# SparrowAprs.net
KiCad netlist of a schematic drawn in EAGLE
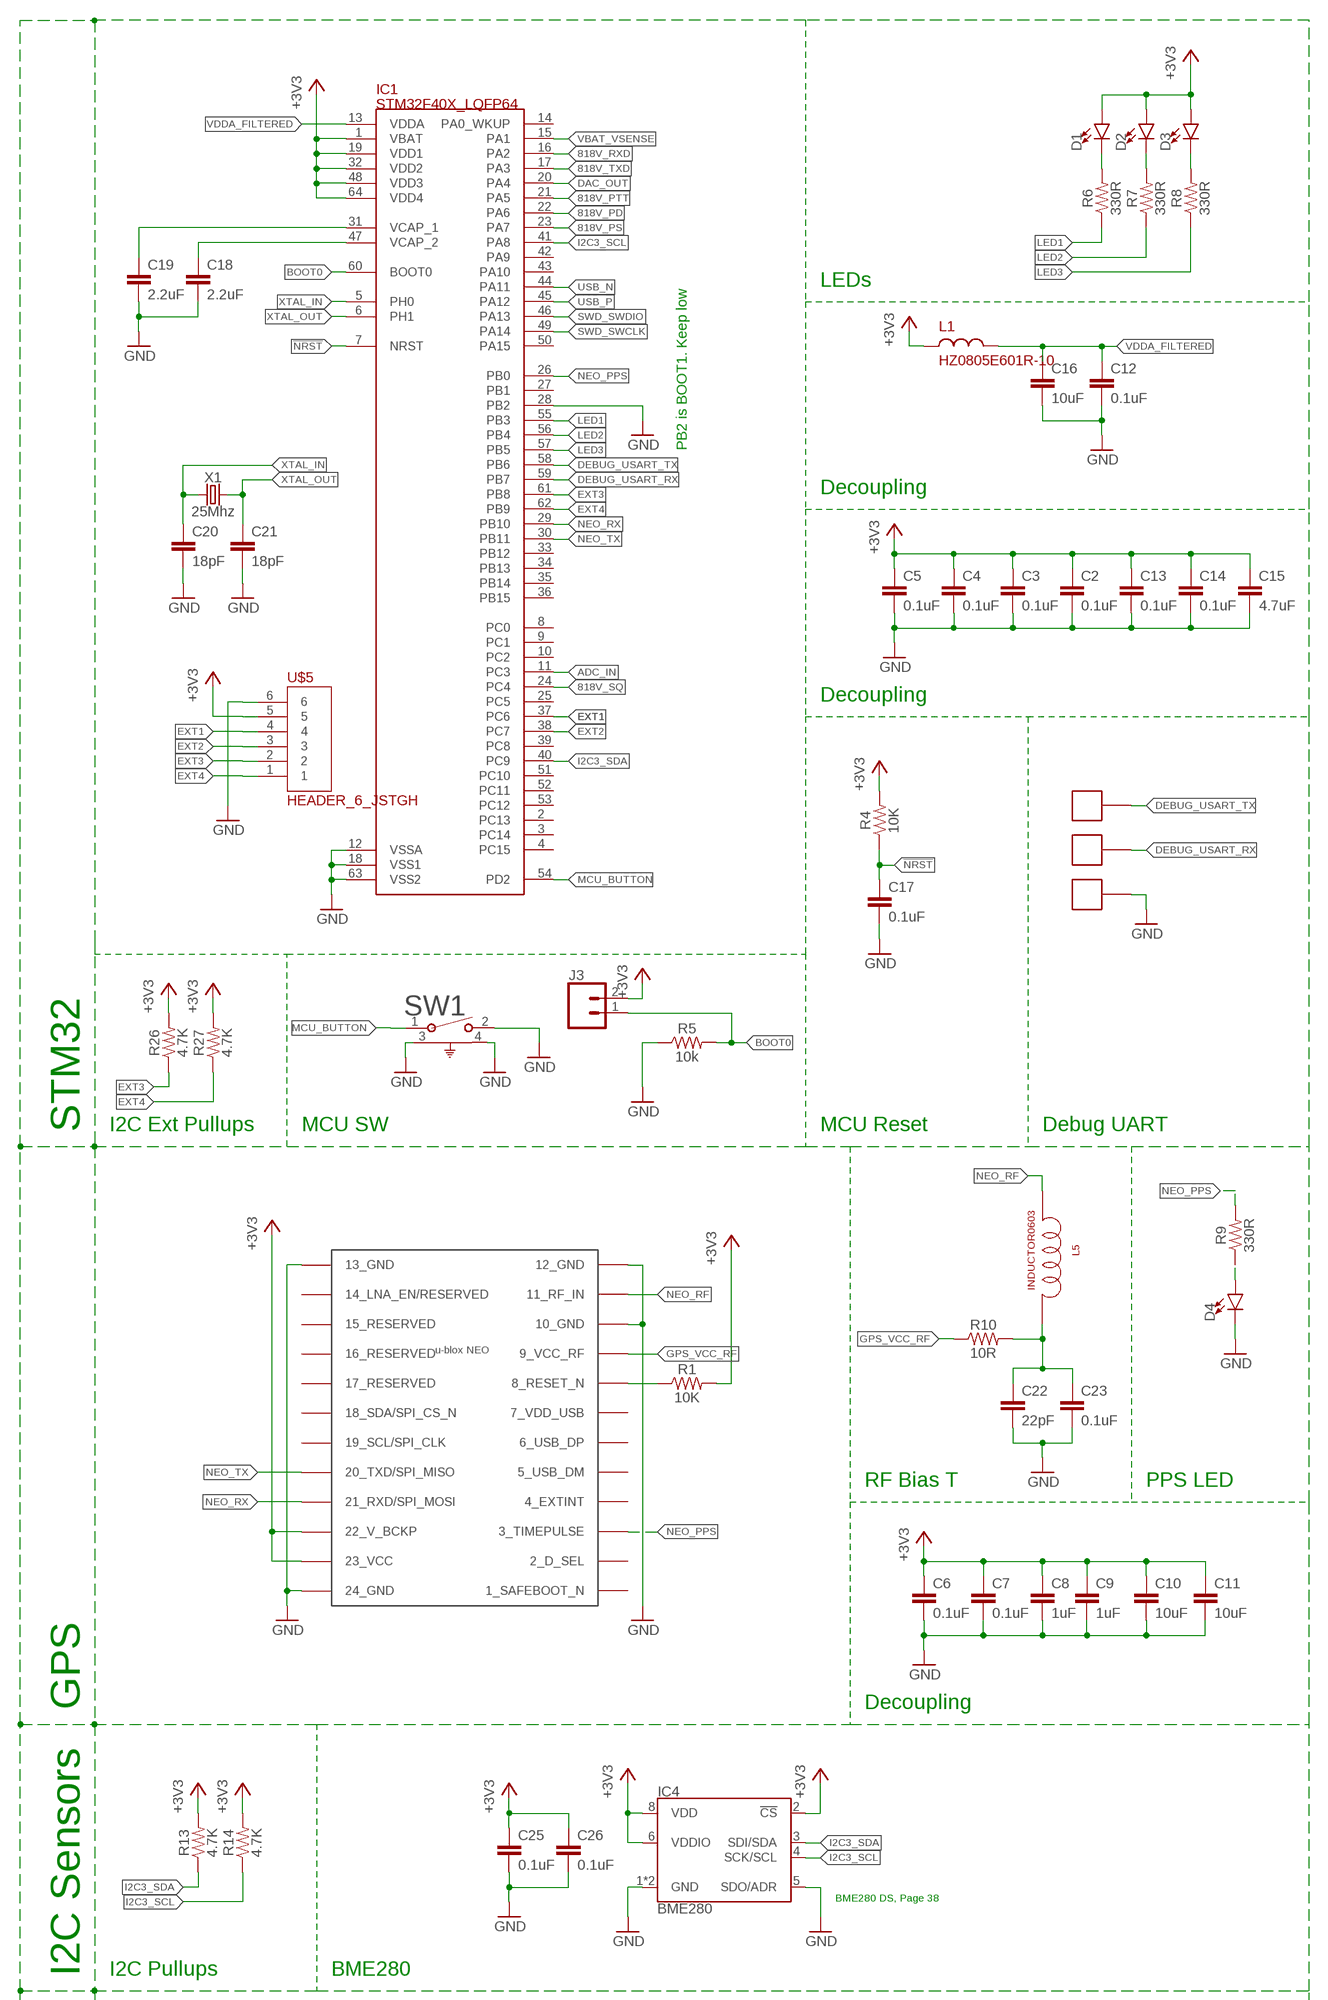
[diagram p0: schematic, sheet 1, part 1 of 2]
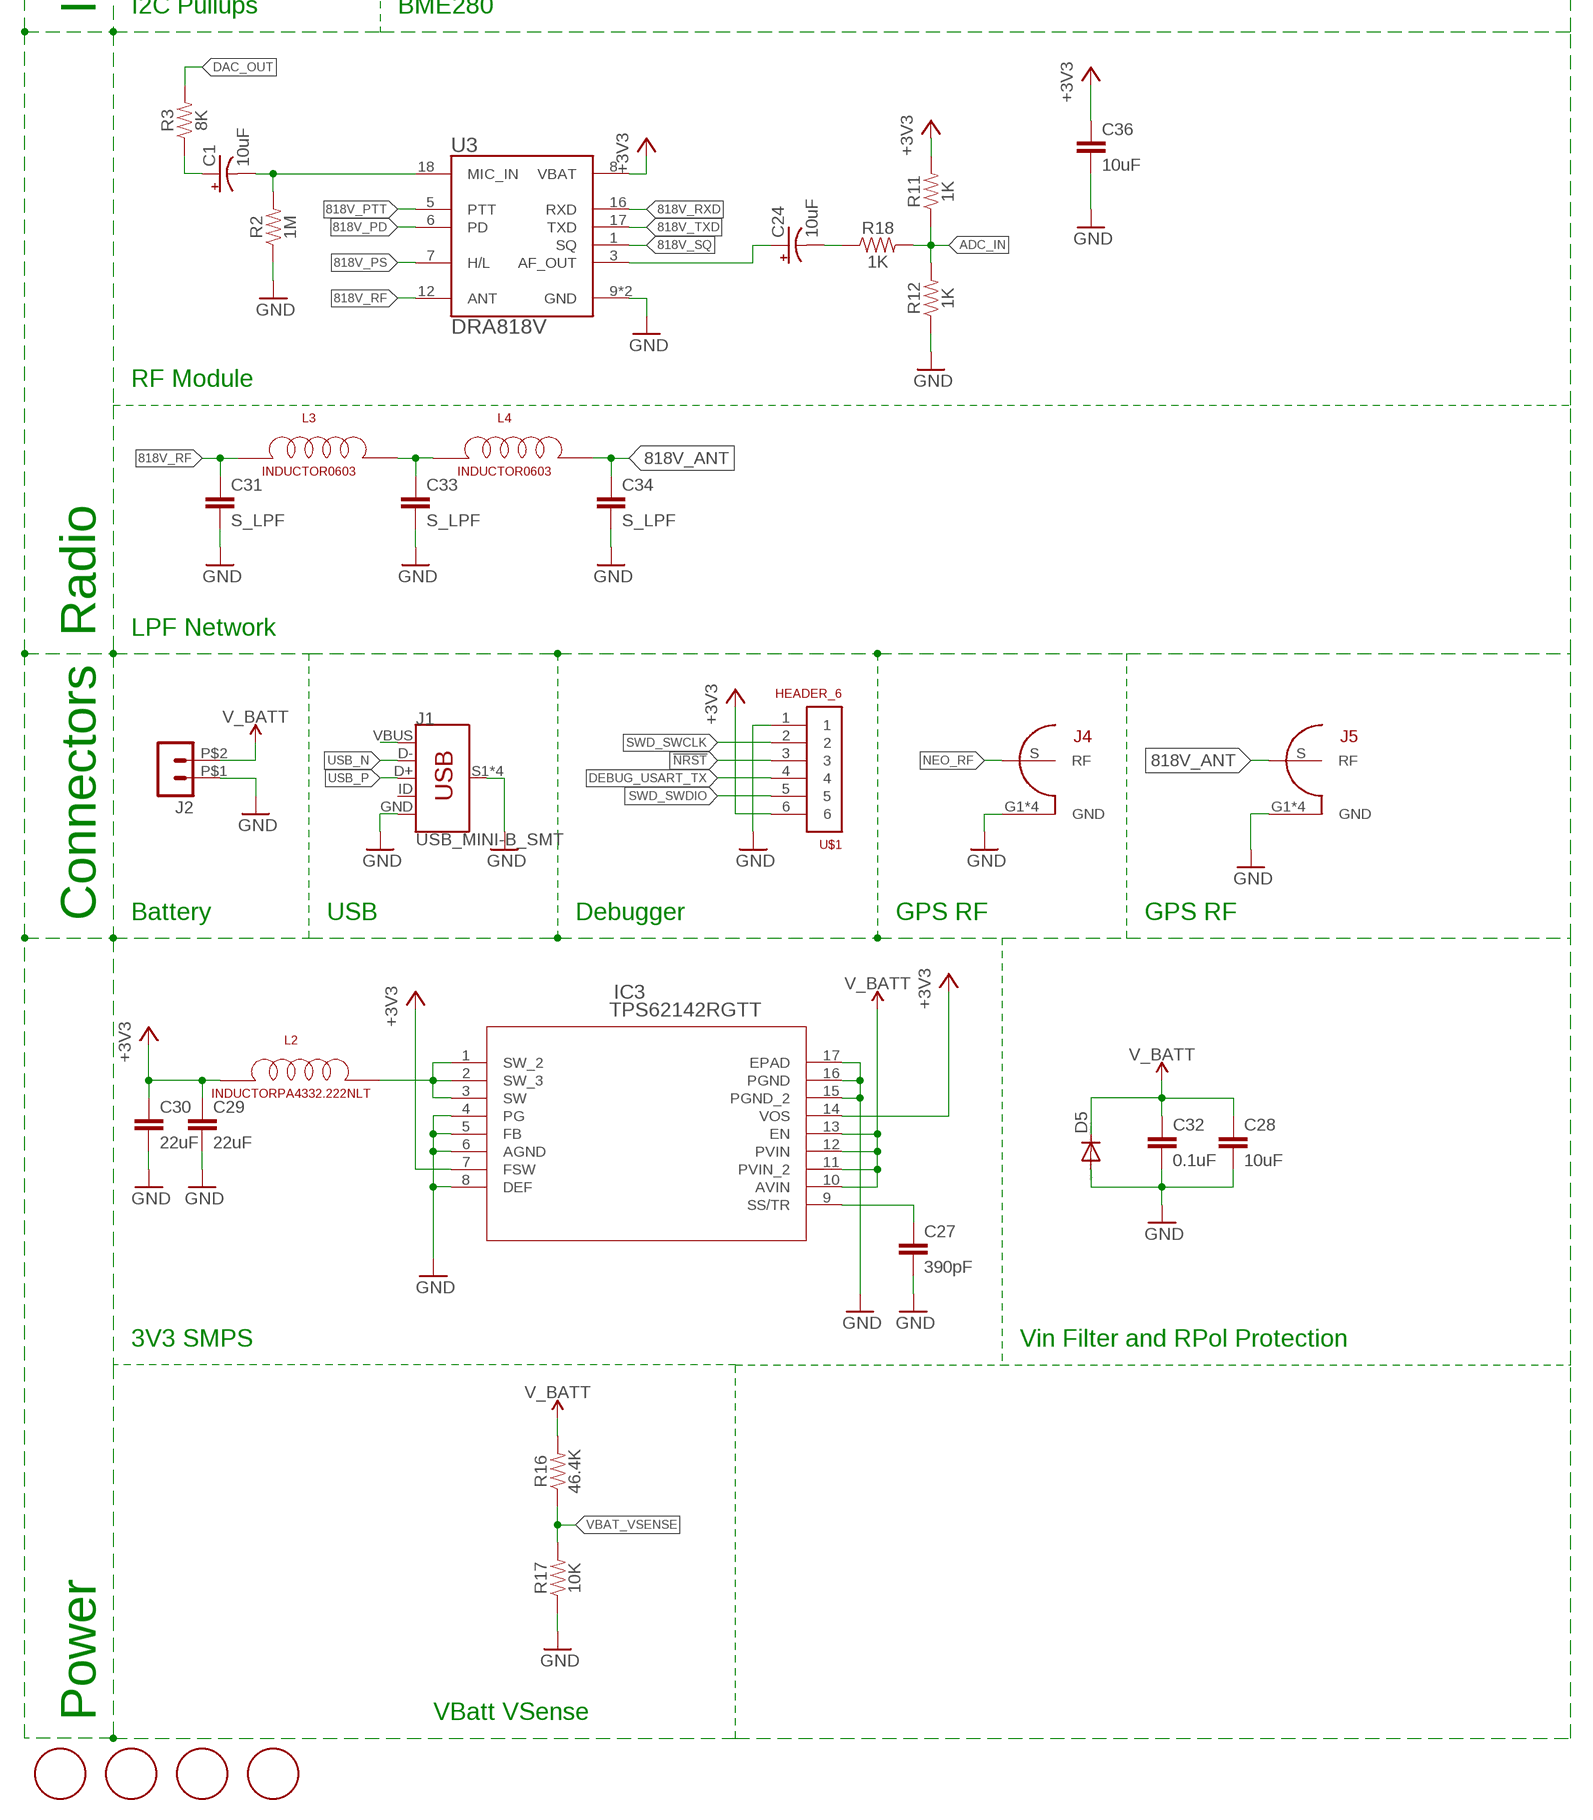
[diagram p1: schematic, sheet 1, part 2 of 2]

(export (version "E")
  (design (tool "Eeschema 10.0.6"))
  (components
    (comp (ref "C1")
      (value "10uF")
      (footprint "eagle-import:1206")
      (libsource (lib "eagle-import") (part "CAP_POL1206_POL"))
    )
    (comp (ref "C2")
      (value "0.1uF")
      (footprint "eagle-import:0603")
      (libsource (lib "eagle-import") (part "CAP0603"))
    )
    (comp (ref "C3")
      (value "0.1uF")
      (footprint "eagle-import:0603")
      (libsource (lib "eagle-import") (part "CAP0603"))
    )
    (comp (ref "C4")
      (value "0.1uF")
      (footprint "eagle-import:0603")
      (libsource (lib "eagle-import") (part "CAP0603"))
    )
    (comp (ref "C5")
      (value "0.1uF")
      (footprint "eagle-import:0603")
      (libsource (lib "eagle-import") (part "CAP0603"))
    )
    (comp (ref "C6")
      (value "0.1uF")
      (footprint "eagle-import:0603")
      (libsource (lib "eagle-import") (part "CAP0603"))
    )
    (comp (ref "C7")
      (value "0.1uF")
      (footprint "eagle-import:0603")
      (libsource (lib "eagle-import") (part "CAP0603"))
    )
    (comp (ref "C8")
      (value "1uF")
      (footprint "eagle-import:C0805")
      (libsource (lib "eagle-import") (part "C-EUC0805"))
    )
    (comp (ref "C9")
      (value "1uF")
      (footprint "eagle-import:C0805")
      (libsource (lib "eagle-import") (part "C-EUC0805"))
    )
    (comp (ref "C10")
      (value "10uF")
      (footprint "eagle-import:C0805")
      (libsource (lib "eagle-import") (part "C-EUC0805"))
    )
    (comp (ref "C11")
      (value "10uF")
      (footprint "eagle-import:C0805")
      (libsource (lib "eagle-import") (part "C-EUC0805"))
    )
    (comp (ref "C12")
      (value "0.1uF")
      (footprint "eagle-import:0603")
      (libsource (lib "eagle-import") (part "CAP0603"))
    )
    (comp (ref "C13")
      (value "0.1uF")
      (footprint "eagle-import:0603")
      (libsource (lib "eagle-import") (part "CAP0603"))
    )
    (comp (ref "C14")
      (value "0.1uF")
      (footprint "eagle-import:0603")
      (libsource (lib "eagle-import") (part "CAP0603"))
    )
    (comp (ref "C15")
      (value "4.7uF")
      (footprint "eagle-import:C0805")
      (libsource (lib "eagle-import") (part "C-EUC0805"))
    )
    (comp (ref "C16")
      (value "10uF")
      (footprint "eagle-import:C0805")
      (libsource (lib "eagle-import") (part "C-EUC0805"))
    )
    (comp (ref "C17")
      (value "0.1uF")
      (footprint "eagle-import:0603")
      (libsource (lib "eagle-import") (part "CAP0603"))
    )
    (comp (ref "C18")
      (value "2.2uF")
      (footprint "eagle-import:C0805")
      (libsource (lib "eagle-import") (part "C-EUC0805"))
    )
    (comp (ref "C19")
      (value "2.2uF")
      (footprint "eagle-import:C0805")
      (libsource (lib "eagle-import") (part "C-EUC0805"))
    )
    (comp (ref "C20")
      (value "18pF")
      (footprint "eagle-import:0603")
      (libsource (lib "eagle-import") (part "CAP0603"))
    )
    (comp (ref "C21")
      (value "18pF")
      (footprint "eagle-import:0603")
      (libsource (lib "eagle-import") (part "CAP0603"))
    )
    (comp (ref "C22")
      (value "22pF")
      (footprint "eagle-import:0603")
      (libsource (lib "eagle-import") (part "CAP0603"))
    )
    (comp (ref "C23")
      (value "0.1uF")
      (footprint "eagle-import:0603")
      (libsource (lib "eagle-import") (part "CAP0603"))
    )
    (comp (ref "C24")
      (value "10uF")
      (footprint "eagle-import:1206")
      (libsource (lib "eagle-import") (part "CAP_POL1206_POL"))
    )
    (comp (ref "C25")
      (value "0.1uF")
      (footprint "eagle-import:0603")
      (libsource (lib "eagle-import") (part "CAP0603"))
    )
    (comp (ref "C26")
      (value "0.1uF")
      (footprint "eagle-import:0603")
      (libsource (lib "eagle-import") (part "CAP0603"))
    )
    (comp (ref "C27")
      (value "390pF")
      (footprint "eagle-import:0603")
      (libsource (lib "eagle-import") (part "CAP0603"))
    )
    (comp (ref "C28")
      (value "10uF")
      (footprint "eagle-import:C0805")
      (libsource (lib "eagle-import") (part "C-EUC0805"))
    )
    (comp (ref "C29")
      (value "22uF")
      (footprint "eagle-import:1210")
      (libsource (lib "eagle-import") (part "CAP1210"))
    )
    (comp (ref "C30")
      (value "22uF")
      (footprint "eagle-import:1210")
      (libsource (lib "eagle-import") (part "CAP1210"))
    )
    (comp (ref "C31")
      (value "S_LPF")
      (footprint "eagle-import:0603")
      (libsource (lib "eagle-import") (part "CAP0603"))
    )
    (comp (ref "C32")
      (value "0.1uF")
      (footprint "eagle-import:0603")
      (libsource (lib "eagle-import") (part "CAP0603"))
    )
    (comp (ref "C33")
      (value "S_LPF")
      (footprint "eagle-import:0603")
      (libsource (lib "eagle-import") (part "CAP0603"))
    )
    (comp (ref "C34")
      (value "S_LPF")
      (footprint "eagle-import:0603")
      (libsource (lib "eagle-import") (part "CAP0603"))
    )
    (comp (ref "C36")
      (value "10uF")
      (footprint "eagle-import:C0805")
      (libsource (lib "eagle-import") (part "C-EUC0805"))
    )
    (comp (ref "D1")
      (value "LED0603")
      (footprint "eagle-import:LED-0603")
      (libsource (lib "eagle-import") (part "LED0603"))
    )
    (comp (ref "D2")
      (value "LED0603")
      (footprint "eagle-import:LED-0603")
      (libsource (lib "eagle-import") (part "LED0603"))
    )
    (comp (ref "D3")
      (value "LED0603")
      (footprint "eagle-import:LED-0603")
      (libsource (lib "eagle-import") (part "LED0603"))
    )
    (comp (ref "D4")
      (value "LED0603")
      (footprint "eagle-import:LED-0603")
      (libsource (lib "eagle-import") (part "LED0603"))
    )
    (comp (ref "D5")
      (value "DIODE-DO214AC")
      (footprint "eagle-import:DO214AC")
      (libsource (lib "eagle-import") (part "DIODE-DO214AC"))
    )
    (comp (ref "IC1")
      (value "STM32F40X_LQFP64")
      (footprint "eagle-import:STM32_LQFP64")
      (libsource (lib "eagle-import") (part "STM32F40X_LQFP64"))
    )
    (comp (ref "IC2")
      (value "NEO-M8")
      (footprint "eagle-import:NEO-M8")
      (libsource (lib "eagle-import") (part "NEO-M8"))
    )
    (comp (ref "IC3")
      (value "TPS62142RGTT")
      (footprint "eagle-import:RGT16_1P7X1P7")
      (libsource (lib "eagle-import") (part "TPS62142RGTT"))
    )
    (comp (ref "IC4")
      (value "BME280")
      (footprint "eagle-import:LGA-8-2.5X2.5")
      (libsource (lib "eagle-import") (part "BME280"))
    )
    (comp (ref "J1")
      (value "USB_MINI-B_SMT")
      (footprint "eagle-import:USB-MINIB")
      (libsource (lib "eagle-import") (part "USB_MINI-B_SMT"))
    )
    (comp (ref "J2")
      (value "HEADER_POS2_43650-0200")
      (footprint "eagle-import:43650-0200")
      (libsource (lib "eagle-import") (part "HEADER_POS2_?43650-0200"))
    )
    (comp (ref "J3")
      (value "CONN_02")
      (footprint "eagle-import:1X02")
      (libsource (lib "eagle-import") (part "CONN_02"))
    )
    (comp (ref "J4")
      (value "FSK_RUARK2_SMA_0732511150")
      (footprint "eagle-import:FSK_RUARK2_WIDE_SMA")
      (libsource (lib "eagle-import") (part "FSK_RUARK2_SMA_0732511150"))
    )
    (comp (ref "J5")
      (value "FSK_RUARK2_SMA_0732511150")
      (footprint "eagle-import:FSK_RUARK2_WIDE_SMA")
      (libsource (lib "eagle-import") (part "FSK_RUARK2_SMA_0732511150"))
    )
    (comp (ref "L1")
      (value "HZ0805E601R-10")
      (footprint "eagle-import:R0805")
      (libsource (lib "eagle-import") (part "HZ0805E601R-10"))
    )
    (comp (ref "L2")
      (value "INDUCTORPA4332.222NLT")
      (footprint "eagle-import:PA4332.222NLT")
      (libsource (lib "eagle-import") (part "INDUCTORPA4332.222NLT"))
    )
    (comp (ref "L3")
      (value "INDUCTOR0603")
      (footprint "eagle-import:0603")
      (libsource (lib "eagle-import") (part "INDUCTOR0603"))
    )
    (comp (ref "L4")
      (value "INDUCTOR0603")
      (footprint "eagle-import:0603")
      (libsource (lib "eagle-import") (part "INDUCTOR0603"))
    )
    (comp (ref "L5")
      (value "INDUCTOR0603")
      (footprint "eagle-import:0603")
      (libsource (lib "eagle-import") (part "INDUCTOR0603"))
    )
    (comp (ref "R1")
      (value "10K")
      (footprint "eagle-import:0603")
      (libsource (lib "eagle-import") (part "RESISTOR0603"))
    )
    (comp (ref "R2")
      (value "1M")
      (footprint "eagle-import:0603")
      (libsource (lib "eagle-import") (part "RESISTOR0603"))
    )
    (comp (ref "R3")
      (value "8K")
      (footprint "eagle-import:0603")
      (libsource (lib "eagle-import") (part "RESISTOR0603"))
    )
    (comp (ref "R4")
      (value "10K")
      (footprint "eagle-import:0603")
      (libsource (lib "eagle-import") (part "RESISTOR0603"))
    )
    (comp (ref "R5")
      (value "10k")
      (footprint "eagle-import:0603")
      (libsource (lib "eagle-import") (part "RESISTOR0603"))
    )
    (comp (ref "R6")
      (value "330R")
      (footprint "eagle-import:0603")
      (libsource (lib "eagle-import") (part "RESISTOR0603"))
    )
    (comp (ref "R7")
      (value "330R")
      (footprint "eagle-import:0603")
      (libsource (lib "eagle-import") (part "RESISTOR0603"))
    )
    (comp (ref "R8")
      (value "330R")
      (footprint "eagle-import:0603")
      (libsource (lib "eagle-import") (part "RESISTOR0603"))
    )
    (comp (ref "R9")
      (value "330R")
      (footprint "eagle-import:0603")
      (libsource (lib "eagle-import") (part "RESISTOR0603"))
    )
    (comp (ref "R10")
      (value "10R")
      (footprint "eagle-import:0603")
      (libsource (lib "eagle-import") (part "RESISTOR0603"))
    )
    (comp (ref "R11")
      (value "1K")
      (footprint "eagle-import:0603")
      (libsource (lib "eagle-import") (part "RESISTOR0603"))
    )
    (comp (ref "R12")
      (value "1K")
      (footprint "eagle-import:0603")
      (libsource (lib "eagle-import") (part "RESISTOR0603"))
    )
    (comp (ref "R13")
      (value "4.7K")
      (footprint "eagle-import:0603")
      (libsource (lib "eagle-import") (part "RESISTOR0603"))
    )
    (comp (ref "R14")
      (value "4.7K")
      (footprint "eagle-import:0603")
      (libsource (lib "eagle-import") (part "RESISTOR0603"))
    )
    (comp (ref "R16")
      (value "46.4K")
      (footprint "eagle-import:0603")
      (libsource (lib "eagle-import") (part "RESISTOR0603"))
    )
    (comp (ref "R17")
      (value "10K")
      (footprint "eagle-import:0603")
      (libsource (lib "eagle-import") (part "RESISTOR0603"))
    )
    (comp (ref "R18")
      (value "1K")
      (footprint "eagle-import:0603")
      (libsource (lib "eagle-import") (part "RESISTOR0603"))
    )
    (comp (ref "R26")
      (value "4.7K")
      (footprint "eagle-import:0603")
      (libsource (lib "eagle-import") (part "RESISTOR0603"))
    )
    (comp (ref "R27")
      (value "4.7K")
      (footprint "eagle-import:0603")
      (libsource (lib "eagle-import") (part "RESISTOR0603"))
    )
    (comp (ref "SW1")
      (value "1825027-8")
      (footprint "eagle-import:SW2_1825027-C")
      (fields (field (name "MANUFACTURER_PART_NUMBER") "18250278"))
      (libsource (lib "eagle-import") (part "1825027-8"))
    )
    (comp (ref "U$1")
      (value "HEADER_6")
      (footprint "eagle-import:6X2_SMT")
      (libsource (lib "eagle-import") (part "HEADER_6"))
    )
    (comp (ref "U$2")
      (value "SINGLEPADMIDPAD")
      (footprint "eagle-import:MIDPAD")
      (libsource (lib "eagle-import") (part "SINGLEPADMIDPAD"))
    )
    (comp (ref "U$3")
      (value "SINGLEPADMIDPAD")
      (footprint "eagle-import:MIDPAD")
      (libsource (lib "eagle-import") (part "SINGLEPADMIDPAD"))
    )
    (comp (ref "U$4")
      (value "SINGLEPADMIDPAD")
      (footprint "eagle-import:MIDPAD")
      (libsource (lib "eagle-import") (part "SINGLEPADMIDPAD"))
    )
    (comp (ref "U$5")
      (value "HEADER_6_JSTGH")
      (footprint "eagle-import:BM06B-GHS-TBT(LF)(SN)(N)")
      (libsource (lib "eagle-import") (part "HEADER_6_JSTGH"))
    )
    (comp (ref "U$7")
      (value "MOUNTING_HOLE#2")
      (footprint "eagle-import:#2_CLEARANCE_HOLE")
      (libsource (lib "eagle-import") (part "MOUNTING_HOLE#2"))
    )
    (comp (ref "U$8")
      (value "MOUNTING_HOLE#2")
      (footprint "eagle-import:#2_CLEARANCE_HOLE")
      (libsource (lib "eagle-import") (part "MOUNTING_HOLE#2"))
    )
    (comp (ref "U$9")
      (value "MOUNTING_HOLE#2")
      (footprint "eagle-import:#2_CLEARANCE_HOLE")
      (libsource (lib "eagle-import") (part "MOUNTING_HOLE#2"))
    )
    (comp (ref "U$10")
      (value "MOUNTING_HOLE#2")
      (footprint "eagle-import:#2_CLEARANCE_HOLE")
      (libsource (lib "eagle-import") (part "MOUNTING_HOLE#2"))
    )
    (comp (ref "U3")
      (value "DRA818V")
      (footprint "eagle-import:DORJI_DRA818V")
      (fields (field (name "MF") "DORJI"))
      (libsource (lib "eagle-import") (part "DRA818V"))
    )
    (comp (ref "X1")
      (value "25Mhz")
      (footprint "eagle-import:CRYSTAL-SMD-3.2X2.5MM")
      (libsource (lib "eagle-import") (part "CRYSTALSMD-3.2X2.5"))
    )
  )
  (nets
    (net (code "1") (name "+3V3") (class "Default")
      (node (ref "C10") (pin "1") (pinfunction "1_1") (pintype "passive"))
      (node (ref "C11") (pin "1") (pinfunction "1_1") (pintype "passive"))
      (node (ref "C13") (pin "1") (pinfunction "1_1") (pintype "passive"))
      (node (ref "C14") (pin "1") (pinfunction "1_1") (pintype "passive"))
      (node (ref "C15") (pin "1") (pinfunction "1_1") (pintype "passive"))
      (node (ref "C2") (pin "1") (pinfunction "1_1") (pintype "passive"))
      (node (ref "C25") (pin "1") (pinfunction "1_1") (pintype "passive"))
      (node (ref "C26") (pin "1") (pinfunction "1_1") (pintype "passive"))
      (node (ref "C29") (pin "1") (pinfunction "1_1") (pintype "passive"))
      (node (ref "C3") (pin "1") (pinfunction "1_1") (pintype "passive"))
      (node (ref "C30") (pin "1") (pinfunction "1_1") (pintype "passive"))
      (node (ref "C36") (pin "1") (pinfunction "1_1") (pintype "passive"))
      (node (ref "C4") (pin "1") (pinfunction "1_1") (pintype "passive"))
      (node (ref "C5") (pin "1") (pinfunction "1_1") (pintype "passive"))
      (node (ref "C6") (pin "1") (pinfunction "1_1") (pintype "passive"))
      (node (ref "C7") (pin "1") (pinfunction "1_1") (pintype "passive"))
      (node (ref "C8") (pin "1") (pinfunction "1_1") (pintype "passive"))
      (node (ref "C9") (pin "1") (pinfunction "1_1") (pintype "passive"))
      (node (ref "D1") (pin "A") (pinfunction "A_A") (pintype "passive"))
      (node (ref "D2") (pin "A") (pinfunction "A_A") (pintype "passive"))
      (node (ref "D3") (pin "A") (pinfunction "A_A") (pintype "passive"))
      (node (ref "IC1") (pin "1") (pinfunction "VBAT_1") (pintype "bidirectional"))
      (node (ref "IC1") (pin "19") (pinfunction "VDD1_19") (pintype "bidirectional"))
      (node (ref "IC1") (pin "32") (pinfunction "VDD2_32") (pintype "bidirectional"))
      (node (ref "IC1") (pin "48") (pinfunction "VDD3_48") (pintype "bidirectional"))
      (node (ref "IC1") (pin "64") (pinfunction "VDD4_64") (pintype "bidirectional"))
      (node (ref "IC2") (pin "22") (pinfunction "22_V_BCKP_22") (pintype "bidirectional"))
      (node (ref "IC2") (pin "23") (pinfunction "23_VCC_23") (pintype "bidirectional"))
      (node (ref "IC3") (pin "14") (pinfunction "VOS_14") (pintype "input"))
      (node (ref "IC3") (pin "7") (pinfunction "FSW_7") (pintype "input"))
      (node (ref "IC4") (pin "2") (pinfunction "~{CS}_2") (pintype "bidirectional"))
      (node (ref "IC4") (pin "6") (pinfunction "VDDIO_6") (pintype "bidirectional"))
      (node (ref "IC4") (pin "8") (pinfunction "VDD_8") (pintype "bidirectional"))
      (node (ref "J3") (pin "2") (pinfunction "2_2") (pintype "passive"))
      (node (ref "L1") (pin "1") (pinfunction "1_1") (pintype "passive"))
      (node (ref "L2") (pin "1") (pinfunction "1_1") (pintype "power_in"))
      (node (ref "R1") (pin "2") (pinfunction "2_2") (pintype "passive"))
      (node (ref "R11") (pin "2") (pinfunction "2_2") (pintype "passive"))
      (node (ref "R13") (pin "2") (pinfunction "2_2") (pintype "passive"))
      (node (ref "R14") (pin "2") (pinfunction "2_2") (pintype "passive"))
      (node (ref "R26") (pin "2") (pinfunction "2_2") (pintype "passive"))
      (node (ref "R27") (pin "2") (pinfunction "2_2") (pintype "passive"))
      (node (ref "R4") (pin "2") (pinfunction "2_2") (pintype "passive"))
      (node (ref "U$1") (pin "6") (pinfunction "6_6") (pintype "bidirectional"))
      (node (ref "U$5") (pin "5") (pinfunction "5_5") (pintype "bidirectional"))
      (node (ref "U3") (pin "8") (pinfunction "VBAT_8") (pintype "power_in"))
    )
    (net (code "2") (name "/~{NRST}") (class "Default")
      (node (ref "C17") (pin "1") (pinfunction "1_1") (pintype "passive"))
      (node (ref "IC1") (pin "7") (pinfunction "NRST_7") (pintype "bidirectional"))
      (node (ref "R4") (pin "1") (pinfunction "1_1") (pintype "passive"))
      (node (ref "U$1") (pin "3") (pinfunction "3_3") (pintype "bidirectional"))
    )
    (net (code "3") (name "818V_ANT") (class "Default")
      (node (ref "C34") (pin "1") (pinfunction "1_1") (pintype "passive"))
      (node (ref "J5") (pin "S") (pinfunction "RF_S") (pintype "bidirectional"))
      (node (ref "L4") (pin "2") (pinfunction "2_2") (pintype "power_in"))
    )
    (net (code "4") (name "818V_PD") (class "Default")
      (node (ref "IC1") (pin "22") (pinfunction "PA6_22") (pintype "bidirectional"))
      (node (ref "U3") (pin "6") (pinfunction "PD_6") (pintype "input"))
    )
    (net (code "5") (name "818V_PS") (class "Default")
      (node (ref "IC1") (pin "23") (pinfunction "PA7_23") (pintype "bidirectional"))
      (node (ref "U3") (pin "7") (pinfunction "H/L_7") (pintype "input"))
    )
    (net (code "6") (name "818V_PTT") (class "Default")
      (node (ref "IC1") (pin "21") (pinfunction "PA5_21") (pintype "bidirectional"))
      (node (ref "U3") (pin "5") (pinfunction "PTT_5") (pintype "input"))
    )
    (net (code "7") (name "818V_RF") (class "Default")
      (node (ref "C31") (pin "1") (pinfunction "1_1") (pintype "passive"))
      (node (ref "L3") (pin "1") (pinfunction "1_1") (pintype "power_in"))
      (node (ref "U3") (pin "12") (pinfunction "ANT_12") (pintype "passive"))
    )
    (net (code "8") (name "818V_RXD") (class "Default")
      (node (ref "IC1") (pin "16") (pinfunction "PA2_16") (pintype "bidirectional"))
      (node (ref "U3") (pin "16") (pinfunction "RXD_16") (pintype "input"))
    )
    (net (code "9") (name "818V_SQ") (class "Default")
      (node (ref "IC1") (pin "24") (pinfunction "PC4_24") (pintype "bidirectional"))
      (node (ref "U3") (pin "1") (pinfunction "SQ_1") (pintype "output"))
    )
    (net (code "10") (name "818V_TXD") (class "Default")
      (node (ref "IC1") (pin "17") (pinfunction "PA3_17") (pintype "bidirectional"))
      (node (ref "U3") (pin "17") (pinfunction "TXD_17") (pintype "output"))
    )
    (net (code "11") (name "ADC_IN") (class "Default")
      (node (ref "IC1") (pin "11") (pinfunction "PC3_11") (pintype "bidirectional"))
      (node (ref "R11") (pin "1") (pinfunction "1_1") (pintype "passive"))
      (node (ref "R12") (pin "2") (pinfunction "2_2") (pintype "passive"))
      (node (ref "R18") (pin "2") (pinfunction "2_2") (pintype "passive"))
    )
    (net (code "12") (name "BOOT0") (class "Default")
      (node (ref "IC1") (pin "60") (pinfunction "BOOT0_60") (pintype "bidirectional"))
      (node (ref "J3") (pin "1") (pinfunction "1_1") (pintype "passive"))
      (node (ref "R5") (pin "2") (pinfunction "2_2") (pintype "passive"))
    )
    (net (code "13") (name "DAC_OUT") (class "Default")
      (node (ref "IC1") (pin "20") (pinfunction "PA4_20") (pintype "bidirectional"))
      (node (ref "R3") (pin "2") (pinfunction "2_2") (pintype "passive"))
    )
    (net (code "14") (name "DEBUG_USART_RX") (class "Default")
      (node (ref "IC1") (pin "59") (pinfunction "PB7_59") (pintype "bidirectional"))
      (node (ref "U$3") (pin "1") (pinfunction "1_1") (pintype "bidirectional"))
    )
    (net (code "15") (name "DEBUG_USART_TX") (class "Default")
      (node (ref "IC1") (pin "58") (pinfunction "PB6_58") (pintype "bidirectional"))
      (node (ref "U$1") (pin "4") (pinfunction "4_4") (pintype "bidirectional"))
      (node (ref "U$2") (pin "1") (pinfunction "1_1") (pintype "bidirectional"))
    )
    (net (code "16") (name "EXT1") (class "Default")
      (node (ref "IC1") (pin "37") (pinfunction "PC6_37") (pintype "bidirectional"))
      (node (ref "U$5") (pin "4") (pinfunction "4_4") (pintype "bidirectional"))
    )
    (net (code "17") (name "EXT2") (class "Default")
      (node (ref "IC1") (pin "38") (pinfunction "PC7_38") (pintype "bidirectional"))
      (node (ref "U$5") (pin "3") (pinfunction "3_3") (pintype "bidirectional"))
    )
    (net (code "18") (name "EXT3") (class "Default")
      (node (ref "IC1") (pin "61") (pinfunction "PB8_61") (pintype "bidirectional"))
      (node (ref "R26") (pin "1") (pinfunction "1_1") (pintype "passive"))
      (node (ref "U$5") (pin "2") (pinfunction "2_2") (pintype "bidirectional"))
    )
    (net (code "19") (name "EXT4") (class "Default")
      (node (ref "IC1") (pin "62") (pinfunction "PB9_62") (pintype "bidirectional"))
      (node (ref "R27") (pin "1") (pinfunction "1_1") (pintype "passive"))
      (node (ref "U$5") (pin "1") (pinfunction "1_1") (pintype "bidirectional"))
    )
    (net (code "20") (name "GND") (class "Default")
      (node (ref "C10") (pin "2") (pinfunction "2_2") (pintype "passive"))
      (node (ref "C11") (pin "2") (pinfunction "2_2") (pintype "passive"))
      (node (ref "C12") (pin "2") (pinfunction "2_2") (pintype "passive"))
      (node (ref "C13") (pin "2") (pinfunction "2_2") (pintype "passive"))
      (node (ref "C14") (pin "2") (pinfunction "2_2") (pintype "passive"))
      (node (ref "C15") (pin "2") (pinfunction "2_2") (pintype "passive"))
      (node (ref "C16") (pin "2") (pinfunction "2_2") (pintype "passive"))
      (node (ref "C17") (pin "2") (pinfunction "2_2") (pintype "passive"))
      (node (ref "C18") (pin "2") (pinfunction "2_2") (pintype "passive"))
      (node (ref "C19") (pin "2") (pinfunction "2_2") (pintype "passive"))
      (node (ref "C2") (pin "2") (pinfunction "2_2") (pintype "passive"))
      (node (ref "C20") (pin "2") (pinfunction "2_2") (pintype "passive"))
      (node (ref "C21") (pin "2") (pinfunction "2_2") (pintype "passive"))
      (node (ref "C22") (pin "2") (pinfunction "2_2") (pintype "passive"))
      (node (ref "C23") (pin "2") (pinfunction "2_2") (pintype "passive"))
      (node (ref "C25") (pin "2") (pinfunction "2_2") (pintype "passive"))
      (node (ref "C26") (pin "2") (pinfunction "2_2") (pintype "passive"))
      (node (ref "C27") (pin "2") (pinfunction "2_2") (pintype "passive"))
      (node (ref "C28") (pin "2") (pinfunction "2_2") (pintype "passive"))
      (node (ref "C29") (pin "2") (pinfunction "2_2") (pintype "passive"))
      (node (ref "C3") (pin "2") (pinfunction "2_2") (pintype "passive"))
      (node (ref "C30") (pin "2") (pinfunction "2_2") (pintype "passive"))
      (node (ref "C31") (pin "2") (pinfunction "2_2") (pintype "passive"))
      (node (ref "C32") (pin "2") (pinfunction "2_2") (pintype "passive"))
      (node (ref "C33") (pin "2") (pinfunction "2_2") (pintype "passive"))
      (node (ref "C34") (pin "2") (pinfunction "2_2") (pintype "passive"))
      (node (ref "C36") (pin "2") (pinfunction "2_2") (pintype "passive"))
      (node (ref "C4") (pin "2") (pinfunction "2_2") (pintype "passive"))
      (node (ref "C5") (pin "2") (pinfunction "2_2") (pintype "passive"))
      (node (ref "C6") (pin "2") (pinfunction "2_2") (pintype "passive"))
      (node (ref "C7") (pin "2") (pinfunction "2_2") (pintype "passive"))
      (node (ref "C8") (pin "2") (pinfunction "2_2") (pintype "passive"))
      (node (ref "C9") (pin "2") (pinfunction "2_2") (pintype "passive"))
      (node (ref "D4") (pin "C") (pinfunction "C_C") (pintype "passive"))
      (node (ref "D5") (pin "A") (pinfunction "A_A") (pintype "passive"))
      (node (ref "IC1") (pin "12") (pinfunction "VSSA_12") (pintype "bidirectional"))
      (node (ref "IC1") (pin "18") (pinfunction "VSS1_18") (pintype "bidirectional"))
      (node (ref "IC1") (pin "28") (pinfunction "PB2_28") (pintype "bidirectional"))
      (node (ref "IC1") (pin "63") (pinfunction "VSS2_63") (pintype "bidirectional"))
      (node (ref "IC2") (pin "10") (pinfunction "10_GND_10") (pintype "bidirectional"))
      (node (ref "IC2") (pin "12") (pinfunction "12_GND_12") (pintype "bidirectional"))
      (node (ref "IC2") (pin "13") (pinfunction "13_GND_13") (pintype "bidirectional"))
      (node (ref "IC2") (pin "24") (pinfunction "24_GND_24") (pintype "bidirectional"))
      (node (ref "IC3") (pin "15") (pinfunction "PGND_2_15") (pintype "power_in"))
      (node (ref "IC3") (pin "16") (pinfunction "PGND_16") (pintype "power_in"))
      (node (ref "IC3") (pin "17") (pinfunction "EPAD_17") (pintype "passive"))
      (node (ref "IC3") (pin "4") (pinfunction "PG_4") (pintype "output"))
      (node (ref "IC3") (pin "5") (pinfunction "FB_5") (pintype "input"))
      (node (ref "IC3") (pin "6") (pinfunction "AGND_6") (pintype "power_in"))
      (node (ref "IC3") (pin "8") (pinfunction "DEF_8") (pintype "input"))
      (node (ref "IC4") (pin "1") (pinfunction "GND_1") (pintype "bidirectional"))
      (node (ref "IC4") (pin "5") (pinfunction "SDO/ADR_5") (pintype "bidirectional"))
      (node (ref "IC4") (pin "7") (pinfunction "GND_7") (pintype "bidirectional"))
      (node (ref "J1") (pin "GND") (pinfunction "GND_GND") (pintype "power_in"))
      (node (ref "J1") (pin "S1") (pinfunction "SHIELD_S1") (pintype "bidirectional"))
      (node (ref "J1") (pin "S2") (pinfunction "SHIELD_S2") (pintype "bidirectional"))
      (node (ref "J1") (pin "S3") (pinfunction "SHIELD_S3") (pintype "bidirectional"))
      (node (ref "J1") (pin "S4") (pinfunction "SHIELD_S4") (pintype "bidirectional"))
      (node (ref "J2") (pin "P$1") (pinfunction "1_P$1") (pintype "passive"))
      (node (ref "J4") (pin "G1") (pinfunction "GND_G1") (pintype "bidirectional"))
      (node (ref "J4") (pin "G2") (pinfunction "GND_G2") (pintype "bidirectional"))
      (node (ref "J4") (pin "G3") (pinfunction "GND_G3") (pintype "bidirectional"))
      (node (ref "J4") (pin "G4") (pinfunction "GND_G4") (pintype "bidirectional"))
      (node (ref "J5") (pin "G1") (pinfunction "GND_G1") (pintype "bidirectional"))
      (node (ref "J5") (pin "G2") (pinfunction "GND_G2") (pintype "bidirectional"))
      (node (ref "J5") (pin "G3") (pinfunction "GND_G3") (pintype "bidirectional"))
      (node (ref "J5") (pin "G4") (pinfunction "GND_G4") (pintype "bidirectional"))
      (node (ref "R12") (pin "1") (pinfunction "1_1") (pintype "passive"))
      (node (ref "R17") (pin "1") (pinfunction "1_1") (pintype "passive"))
      (node (ref "R2") (pin "1") (pinfunction "1_1") (pintype "passive"))
      (node (ref "R5") (pin "1") (pinfunction "1_1") (pintype "passive"))
      (node (ref "SW1") (pin "2") (pinfunction "2_2") (pintype "passive"))
      (node (ref "SW1") (pin "3") (pinfunction "3_3") (pintype "passive"))
      (node (ref "SW1") (pin "4") (pinfunction "4_4") (pintype "passive"))
      (node (ref "U$1") (pin "1") (pinfunction "1_1") (pintype "bidirectional"))
      (node (ref "U$4") (pin "1") (pinfunction "1_1") (pintype "bidirectional"))
      (node (ref "U$5") (pin "6") (pinfunction "6_6") (pintype "bidirectional"))
      (node (ref "U3") (pin "10") (pinfunction "GND_10") (pintype "power_in"))
      (node (ref "U3") (pin "9") (pinfunction "GND_9") (pintype "power_in"))
    )
    (net (code "21") (name "GPS_VCC_RF") (class "Default")
      (node (ref "IC2") (pin "9") (pinfunction "9_VCC_RF_9") (pintype "bidirectional"))
      (node (ref "R10") (pin "1") (pinfunction "1_1") (pintype "passive"))
    )
    (net (code "22") (name "I2C3_SCL") (class "Default")
      (node (ref "IC1") (pin "41") (pinfunction "PA8_41") (pintype "bidirectional"))
      (node (ref "IC4") (pin "4") (pinfunction "SCK/SCL_4") (pintype "bidirectional"))
      (node (ref "R14") (pin "1") (pinfunction "1_1") (pintype "passive"))
    )
    (net (code "23") (name "I2C3_SDA") (class "Default")
      (node (ref "IC1") (pin "40") (pinfunction "PC9_40") (pintype "bidirectional"))
      (node (ref "IC4") (pin "3") (pinfunction "SDI/SDA_3") (pintype "bidirectional"))
      (node (ref "R13") (pin "1") (pinfunction "1_1") (pintype "passive"))
    )
    (net (code "24") (name "LED1") (class "Default")
      (node (ref "IC1") (pin "55") (pinfunction "PB3_55") (pintype "bidirectional"))
      (node (ref "R6") (pin "1") (pinfunction "1_1") (pintype "passive"))
    )
    (net (code "25") (name "LED2") (class "Default")
      (node (ref "IC1") (pin "56") (pinfunction "PB4_56") (pintype "bidirectional"))
      (node (ref "R7") (pin "1") (pinfunction "1_1") (pintype "passive"))
    )
    (net (code "26") (name "LED3") (class "Default")
      (node (ref "IC1") (pin "57") (pinfunction "PB5_57") (pintype "bidirectional"))
      (node (ref "R8") (pin "1") (pinfunction "1_1") (pintype "passive"))
    )
    (net (code "27") (name "MCU_BUTTON") (class "Default")
      (node (ref "IC1") (pin "54") (pinfunction "PD2_54") (pintype "bidirectional"))
      (node (ref "SW1") (pin "1") (pinfunction "1_1") (pintype "passive"))
    )
    (net (code "28") (name "NEO_PPS") (class "Default")
      (node (ref "IC1") (pin "26") (pinfunction "PB0_26") (pintype "bidirectional"))
      (node (ref "IC2") (pin "3") (pinfunction "3_TIMEPULSE_3") (pintype "bidirectional"))
      (node (ref "R9") (pin "2") (pinfunction "2_2") (pintype "passive"))
    )
    (net (code "29") (name "NEO_RF") (class "Default")
      (node (ref "IC2") (pin "11") (pinfunction "11_RF_IN_11") (pintype "bidirectional"))
      (node (ref "J4") (pin "S") (pinfunction "RF_S") (pintype "bidirectional"))
      (node (ref "L5") (pin "1") (pinfunction "1_1") (pintype "power_in"))
    )
    (net (code "30") (name "NEO_RX") (class "Default")
      (node (ref "IC1") (pin "29") (pinfunction "PB10_29") (pintype "bidirectional"))
      (node (ref "IC2") (pin "21") (pinfunction "21_RXD/SPI_MOSI_21") (pintype "bidirectional"))
    )
    (net (code "31") (name "NEO_TX") (class "Default")
      (node (ref "IC1") (pin "30") (pinfunction "PB11_30") (pintype "bidirectional"))
      (node (ref "IC2") (pin "20") (pinfunction "20_TXD/SPI_MISO_20") (pintype "bidirectional"))
    )
    (net (code "32") (name "Net-(C1-+)") (class "Default")
      (node (ref "C1") (pin "1") (pinfunction "+_1") (pintype "passive"))
      (node (ref "R3") (pin "1") (pinfunction "1_1") (pintype "passive"))
    )
    (net (code "33") (name "Net-(C1--)") (class "Default")
      (node (ref "C1") (pin "2") (pinfunction "-_2") (pintype "passive"))
      (node (ref "R2") (pin "2") (pinfunction "2_2") (pintype "passive"))
      (node (ref "U3") (pin "18") (pinfunction "MIC_IN_18") (pintype "input"))
    )
    (net (code "34") (name "Net-(C22-Pad1)") (class "Default")
      (node (ref "C22") (pin "1") (pinfunction "1_1") (pintype "passive"))
      (node (ref "C23") (pin "1") (pinfunction "1_1") (pintype "passive"))
      (node (ref "L5") (pin "2") (pinfunction "2_2") (pintype "power_in"))
      (node (ref "R10") (pin "2") (pinfunction "2_2") (pintype "passive"))
    )
    (net (code "35") (name "Net-(C24-+)") (class "Default")
      (node (ref "C24") (pin "1") (pinfunction "+_1") (pintype "passive"))
      (node (ref "U3") (pin "3") (pinfunction "AF_OUT_3") (pintype "output"))
    )
    (net (code "36") (name "Net-(C24--)") (class "Default")
      (node (ref "C24") (pin "2") (pinfunction "-_2") (pintype "passive"))
      (node (ref "R18") (pin "1") (pinfunction "1_1") (pintype "passive"))
    )
    (net (code "37") (name "Net-(C33-Pad1)") (class "Default")
      (node (ref "C33") (pin "1") (pinfunction "1_1") (pintype "passive"))
      (node (ref "L3") (pin "2") (pinfunction "2_2") (pintype "power_in"))
      (node (ref "L4") (pin "1") (pinfunction "1_1") (pintype "power_in"))
    )
    (net (code "38") (name "Net-(D1-PadC)") (class "Default")
      (node (ref "D1") (pin "C") (pinfunction "C_C") (pintype "passive"))
      (node (ref "R6") (pin "2") (pinfunction "2_2") (pintype "passive"))
    )
    (net (code "39") (name "Net-(D2-PadC)") (class "Default")
      (node (ref "D2") (pin "C") (pinfunction "C_C") (pintype "passive"))
      (node (ref "R7") (pin "2") (pinfunction "2_2") (pintype "passive"))
    )
    (net (code "40") (name "Net-(D3-PadC)") (class "Default")
      (node (ref "D3") (pin "C") (pinfunction "C_C") (pintype "passive"))
      (node (ref "R8") (pin "2") (pinfunction "2_2") (pintype "passive"))
    )
    (net (code "41") (name "Net-(D4-PadA)") (class "Default")
      (node (ref "D4") (pin "A") (pinfunction "A_A") (pintype "passive"))
      (node (ref "R9") (pin "1") (pinfunction "1_1") (pintype "passive"))
    )
    (net (code "42") (name "Net-(IC1-VCAP_1)") (class "Default")
      (node (ref "C19") (pin "1") (pinfunction "1_1") (pintype "passive"))
      (node (ref "IC1") (pin "31") (pinfunction "VCAP_1_31") (pintype "bidirectional"))
    )
    (net (code "43") (name "Net-(IC1-VCAP_2)") (class "Default")
      (node (ref "C18") (pin "1") (pinfunction "1_1") (pintype "passive"))
      (node (ref "IC1") (pin "47") (pinfunction "VCAP_2_47") (pintype "bidirectional"))
    )
    (net (code "44") (name "Net-(IC2-8_RESET_N)") (class "Default")
      (node (ref "IC2") (pin "8") (pinfunction "8_RESET_N_8") (pintype "bidirectional"))
      (node (ref "R1") (pin "1") (pinfunction "1_1") (pintype "passive"))
    )
    (net (code "45") (name "Net-(IC3-SS{slash}TR)") (class "Default")
      (node (ref "C27") (pin "1") (pinfunction "1_1") (pintype "passive"))
      (node (ref "IC3") (pin "9") (pinfunction "SS/TR_9") (pintype "input"))
    )
    (net (code "46") (name "Net-(IC3-SW)") (class "Default")
      (node (ref "IC3") (pin "1") (pinfunction "SW_2_1") (pintype "output"))
      (node (ref "IC3") (pin "2") (pinfunction "SW_3_2") (pintype "output"))
      (node (ref "IC3") (pin "3") (pinfunction "SW_3") (pintype "output"))
      (node (ref "L2") (pin "2") (pinfunction "2_2") (pintype "power_in"))
    )
    (net (code "47") (name "SWD_SWCLK") (class "Default")
      (node (ref "IC1") (pin "49") (pinfunction "PA14_49") (pintype "bidirectional"))
      (node (ref "U$1") (pin "2") (pinfunction "2_2") (pintype "bidirectional"))
    )
    (net (code "48") (name "SWD_SWDIO") (class "Default")
      (node (ref "IC1") (pin "46") (pinfunction "PA13_46") (pintype "bidirectional"))
      (node (ref "U$1") (pin "5") (pinfunction "5_5") (pintype "bidirectional"))
    )
    (net (code "49") (name "USB_N") (class "Default")
      (node (ref "IC1") (pin "44") (pinfunction "PA11_44") (pintype "bidirectional"))
      (node (ref "J1") (pin "D-") (pinfunction "D-_D-") (pintype "bidirectional"))
    )
    (net (code "50") (name "USB_P") (class "Default")
      (node (ref "IC1") (pin "45") (pinfunction "PA12_45") (pintype "bidirectional"))
      (node (ref "J1") (pin "D+") (pinfunction "D+_D+") (pintype "bidirectional"))
    )
    (net (code "51") (name "VBAT_VSENSE") (class "Default")
      (node (ref "IC1") (pin "15") (pinfunction "PA1_15") (pintype "bidirectional"))
      (node (ref "R16") (pin "1") (pinfunction "1_1") (pintype "passive"))
      (node (ref "R17") (pin "2") (pinfunction "2_2") (pintype "passive"))
    )
    (net (code "52") (name "VDDA_FILTERED") (class "Default")
      (node (ref "C12") (pin "1") (pinfunction "1_1") (pintype "passive"))
      (node (ref "C16") (pin "1") (pinfunction "1_1") (pintype "passive"))
      (node (ref "IC1") (pin "13") (pinfunction "VDDA_13") (pintype "bidirectional"))
      (node (ref "L1") (pin "2") (pinfunction "2_2") (pintype "passive"))
    )
    (net (code "53") (name "V_BATT") (class "Default")
      (node (ref "C28") (pin "1") (pinfunction "1_1") (pintype "passive"))
      (node (ref "C32") (pin "1") (pinfunction "1_1") (pintype "passive"))
      (node (ref "D5") (pin "C") (pinfunction "C_C") (pintype "passive"))
      (node (ref "IC3") (pin "10") (pinfunction "AVIN_10") (pintype "input"))
      (node (ref "IC3") (pin "11") (pinfunction "PVIN_2_11") (pintype "input"))
      (node (ref "IC3") (pin "12") (pinfunction "PVIN_12") (pintype "input"))
      (node (ref "IC3") (pin "13") (pinfunction "EN_13") (pintype "input"))
      (node (ref "J2") (pin "P$2") (pinfunction "2_P$2") (pintype "passive"))
      (node (ref "R16") (pin "2") (pinfunction "2_2") (pintype "passive"))
    )
    (net (code "54") (name "XTAL_IN") (class "Default")
      (node (ref "C20") (pin "1") (pinfunction "1_1") (pintype "passive"))
      (node (ref "IC1") (pin "5") (pinfunction "PH0_5") (pintype "bidirectional"))
      (node (ref "X1") (pin "1") (pinfunction "1_1") (pintype "passive"))
    )
    (net (code "55") (name "XTAL_OUT") (class "Default")
      (node (ref "C21") (pin "1") (pinfunction "1_1") (pintype "passive"))
      (node (ref "IC1") (pin "6") (pinfunction "PH1_6") (pintype "bidirectional"))
      (node (ref "X1") (pin "3") (pinfunction "2_3") (pintype "passive"))
    )
    (net (code "56") (name "unconnected-(IC1-PA0_WKUP-Pad14)") (class "Default")
      (node (ref "IC1") (pin "14") (pinfunction "PA0_WKUP_14") (pintype "bidirectional"))
    )
    (net (code "57") (name "unconnected-(IC1-PA9-Pad42)") (class "Default")
      (node (ref "IC1") (pin "42") (pinfunction "PA9_42") (pintype "bidirectional"))
    )
    (net (code "58") (name "unconnected-(IC1-PA10-Pad43)") (class "Default")
      (node (ref "IC1") (pin "43") (pinfunction "PA10_43") (pintype "bidirectional"))
    )
    (net (code "59") (name "unconnected-(IC1-PA15-Pad50)") (class "Default")
      (node (ref "IC1") (pin "50") (pinfunction "PA15_50") (pintype "bidirectional"))
    )
    (net (code "60") (name "unconnected-(IC1-PB1-Pad27)") (class "Default")
      (node (ref "IC1") (pin "27") (pinfunction "PB1_27") (pintype "bidirectional"))
    )
    (net (code "61") (name "unconnected-(IC1-PB12-Pad33)") (class "Default")
      (node (ref "IC1") (pin "33") (pinfunction "PB12_33") (pintype "bidirectional"))
    )
    (net (code "62") (name "unconnected-(IC1-PB13-Pad34)") (class "Default")
      (node (ref "IC1") (pin "34") (pinfunction "PB13_34") (pintype "bidirectional"))
    )
    (net (code "63") (name "unconnected-(IC1-PB14-Pad35)") (class "Default")
      (node (ref "IC1") (pin "35") (pinfunction "PB14_35") (pintype "bidirectional"))
    )
    (net (code "64") (name "unconnected-(IC1-PB15-Pad36)") (class "Default")
      (node (ref "IC1") (pin "36") (pinfunction "PB15_36") (pintype "bidirectional"))
    )
    (net (code "65") (name "unconnected-(IC1-PC0-Pad8)") (class "Default")
      (node (ref "IC1") (pin "8") (pinfunction "PC0_8") (pintype "bidirectional"))
    )
    (net (code "66") (name "unconnected-(IC1-PC1-Pad9)") (class "Default")
      (node (ref "IC1") (pin "9") (pinfunction "PC1_9") (pintype "bidirectional"))
    )
    (net (code "67") (name "unconnected-(IC1-PC2-Pad10)") (class "Default")
      (node (ref "IC1") (pin "10") (pinfunction "PC2_10") (pintype "bidirectional"))
    )
    (net (code "68") (name "unconnected-(IC1-PC5-Pad25)") (class "Default")
      (node (ref "IC1") (pin "25") (pinfunction "PC5_25") (pintype "bidirectional"))
    )
    (net (code "69") (name "unconnected-(IC1-PC8-Pad39)") (class "Default")
      (node (ref "IC1") (pin "39") (pinfunction "PC8_39") (pintype "bidirectional"))
    )
    (net (code "70") (name "unconnected-(IC1-PC10-Pad51)") (class "Default")
      (node (ref "IC1") (pin "51") (pinfunction "PC10_51") (pintype "bidirectional"))
    )
    (net (code "71") (name "unconnected-(IC1-PC11-Pad52)") (class "Default")
      (node (ref "IC1") (pin "52") (pinfunction "PC11_52") (pintype "bidirectional"))
    )
    (net (code "72") (name "unconnected-(IC1-PC12-Pad53)") (class "Default")
      (node (ref "IC1") (pin "53") (pinfunction "PC12_53") (pintype "bidirectional"))
    )
    (net (code "73") (name "unconnected-(IC1-PC13-Pad2)") (class "Default")
      (node (ref "IC1") (pin "2") (pinfunction "PC13_2") (pintype "bidirectional"))
    )
    (net (code "74") (name "unconnected-(IC1-PC14-Pad3)") (class "Default")
      (node (ref "IC1") (pin "3") (pinfunction "PC14_3") (pintype "bidirectional"))
    )
    (net (code "75") (name "unconnected-(IC1-PC15-Pad4)") (class "Default")
      (node (ref "IC1") (pin "4") (pinfunction "PC15_4") (pintype "bidirectional"))
    )
    (net (code "76") (name "unconnected-(IC2-1_SAFEBOOT_N-Pad1)") (class "Default")
      (node (ref "IC2") (pin "1") (pinfunction "1_SAFEBOOT_N_1") (pintype "bidirectional"))
    )
    (net (code "77") (name "unconnected-(IC2-2_D_SEL-Pad2)") (class "Default")
      (node (ref "IC2") (pin "2") (pinfunction "2_D_SEL_2") (pintype "bidirectional"))
    )
    (net (code "78") (name "unconnected-(IC2-4_EXTINT-Pad4)") (class "Default")
      (node (ref "IC2") (pin "4") (pinfunction "4_EXTINT_4") (pintype "bidirectional"))
    )
    (net (code "79") (name "unconnected-(IC2-5_USB_DM-Pad5)") (class "Default")
      (node (ref "IC2") (pin "5") (pinfunction "5_USB_DM_5") (pintype "bidirectional"))
    )
    (net (code "80") (name "unconnected-(IC2-6_USB_DP-Pad6)") (class "Default")
      (node (ref "IC2") (pin "6") (pinfunction "6_USB_DP_6") (pintype "bidirectional"))
    )
    (net (code "81") (name "unconnected-(IC2-7_VDD_USB-Pad7)") (class "Default")
      (node (ref "IC2") (pin "7") (pinfunction "7_VDD_USB_7") (pintype "bidirectional"))
    )
    (net (code "82") (name "unconnected-(IC2-14_LNA_EN{slash}RESERVED-Pad14)") (class "Default")
      (node (ref "IC2") (pin "14") (pinfunction "14_LNA_EN/RESERVED_14") (pintype "bidirectional"))
    )
    (net (code "83") (name "unconnected-(IC2-15_RESERVED-Pad15)") (class "Default")
      (node (ref "IC2") (pin "15") (pinfunction "15_RESERVED_15") (pintype "bidirectional"))
    )
    (net (code "84") (name "unconnected-(IC2-16_RESERVED-Pad16)") (class "Default")
      (node (ref "IC2") (pin "16") (pinfunction "16_RESERVED_16") (pintype "bidirectional"))
    )
    (net (code "85") (name "unconnected-(IC2-17_RESERVED-Pad17)") (class "Default")
      (node (ref "IC2") (pin "17") (pinfunction "17_RESERVED_17") (pintype "bidirectional"))
    )
    (net (code "86") (name "unconnected-(IC2-18_SDA{slash}SPI_CS_N-Pad18)") (class "Default")
      (node (ref "IC2") (pin "18") (pinfunction "18_SDA/SPI_CS_N_18") (pintype "bidirectional"))
    )
    (net (code "87") (name "unconnected-(IC2-19_SCL{slash}SPI_CLK-Pad19)") (class "Default")
      (node (ref "IC2") (pin "19") (pinfunction "19_SCL/SPI_CLK_19") (pintype "bidirectional"))
    )
    (net (code "88") (name "unconnected-(J1-PadID)") (class "Default")
      (node (ref "J1") (pin "ID") (pinfunction "ID_ID") (pintype "bidirectional"))
    )
    (net (code "89") (name "unconnected-(J1-PadVBUS)") (class "Default")
      (node (ref "J1") (pin "VBUS") (pinfunction "VBUS_VBUS") (pintype "power_in"))
    )
  )
)
